# PFet_Breakout.net
KiCad netlist of a schematic drawn in EAGLE
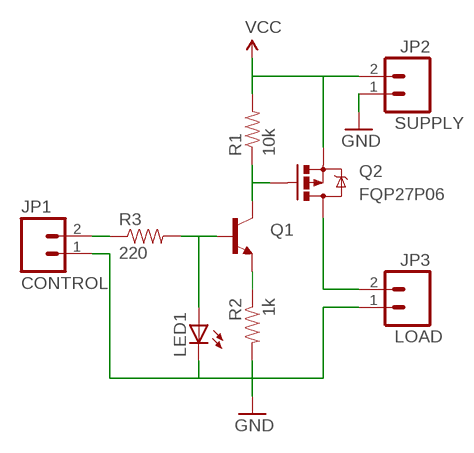
[diagram p0: schematic, sheet 1]

(export (version "E")
  (design (tool "Eeschema 10.0.6"))
  (components
    (comp (ref "JP1")
      (value "M02PTH")
      (footprint "eagle-import:1X02")
      (libsource (lib "eagle-import") (part "M02PTH"))
    )
    (comp (ref "JP2")
      (value "M023.5MM")
      (footprint "eagle-import:SCREWTERMINAL-3.5MM-2")
      (libsource (lib "eagle-import") (part "M023.5MM"))
    )
    (comp (ref "JP3")
      (value "M023.5MM")
      (footprint "eagle-import:SCREWTERMINAL-3.5MM-2")
      (libsource (lib "eagle-import") (part "M023.5MM"))
    )
    (comp (ref "LED1")
      (value "LED5MM")
      (footprint "eagle-import:LED5MM")
      (libsource (lib "eagle-import") (part "LED5MM"))
    )
    (comp (ref "Q1")
      (value "TRANSISTOR_NPNP2N2222A")
      (footprint "eagle-import:TO-92")
      (libsource (lib "eagle-import") (part "TRANSISTOR_NPNP2N2222A"))
    )
    (comp (ref "Q2")
      (value "MOSFET-PCHANNELFQP27P06")
      (footprint "eagle-import:TO220V")
      (libsource (lib "eagle-import") (part "MOSFET-PCHANNELFQP27P06"))
    )
    (comp (ref "R1")
      (value "10k")
      (footprint "eagle-import:AXIAL-0.3")
      (libsource (lib "eagle-import") (part "RESISTORAXIAL-0.3"))
    )
    (comp (ref "R2")
      (value "1k")
      (footprint "eagle-import:AXIAL-0.3")
      (libsource (lib "eagle-import") (part "RESISTORAXIAL-0.3"))
    )
    (comp (ref "R3")
      (value "220")
      (footprint "eagle-import:AXIAL-0.3")
      (libsource (lib "eagle-import") (part "RESISTORAXIAL-0.3"))
    )
  )
  (nets
    (net (code "1") (name "GND") (class "Default")
      (node (ref "JP1") (pin "1") (pinfunction "1_1") (pintype "passive"))
      (node (ref "JP2") (pin "1") (pinfunction "1_1") (pintype "passive"))
      (node (ref "JP3") (pin "1") (pinfunction "1_1") (pintype "passive"))
      (node (ref "LED1") (pin "K") (pinfunction "C_K") (pintype "passive"))
      (node (ref "R2") (pin "P$2") (pinfunction "2_P$2") (pintype "passive"))
    )
    (net (code "2") (name "Net-(Q1-B)") (class "Default")
      (node (ref "LED1") (pin "A") (pinfunction "A_A") (pintype "passive"))
      (node (ref "Q1") (pin "2") (pinfunction "B_2") (pintype "passive"))
      (node (ref "R3") (pin "P$2") (pinfunction "2_P$2") (pintype "passive"))
    )
    (net (code "3") (name "Net-(Q1-C)") (class "Default")
      (node (ref "Q1") (pin "1") (pinfunction "C_1") (pintype "passive"))
      (node (ref "Q2") (pin "1") (pinfunction "G_1") (pintype "passive"))
      (node (ref "R1") (pin "P$1") (pinfunction "1_P$1") (pintype "passive"))
    )
    (net (code "4") (name "Net-(Q1-E)") (class "Default")
      (node (ref "Q1") (pin "3") (pinfunction "E_3") (pintype "passive"))
      (node (ref "R2") (pin "P$1") (pinfunction "1_P$1") (pintype "passive"))
    )
    (net (code "5") (name "Net-(Q2-D)") (class "Default")
      (node (ref "JP3") (pin "2") (pinfunction "2_2") (pintype "passive"))
      (node (ref "Q2") (pin "2") (pinfunction "D_2") (pintype "passive"))
    )
    (net (code "6") (name "Net-(R3-1)") (class "Default")
      (node (ref "JP1") (pin "2") (pinfunction "2_2") (pintype "passive"))
      (node (ref "R3") (pin "P$1") (pinfunction "1_P$1") (pintype "passive"))
    )
    (net (code "7") (name "VCC") (class "Default")
      (node (ref "JP2") (pin "2") (pinfunction "2_2") (pintype "passive"))
      (node (ref "Q2") (pin "3") (pinfunction "S_3") (pintype "passive"))
      (node (ref "R1") (pin "P$2") (pinfunction "2_P$2") (pintype "passive"))
    )
  )
)
